# hexapod_mk2_leg_v0_0.net
KiCad netlist of a schematic drawn in EAGLE
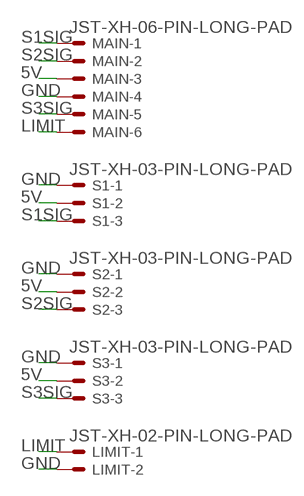
[diagram p0: schematic, sheet 1]

(export (version "E")
  (design (tool "Eeschema 10.0.6"))
  (components
    (comp (ref "LIMIT")
      (value "JST-XH-02-PIN-LONG-PAD")
      (footprint "eagle-import:JST-XH-02-PACKAGE-LONG-PAD")
      (libsource (lib "eagle-import") (part "JST-XH-02-PIN-LONG-PAD"))
    )
    (comp (ref "MAIN")
      (value "JST-XH-06-PIN-LONG-PAD")
      (footprint "eagle-import:JST-XH-06-PACKAGE-LONG-PAD")
      (libsource (lib "eagle-import") (part "JST-XH-06-PIN-LONG-PAD"))
    )
    (comp (ref "S1")
      (value "JST-XH-03-PIN-LONG-PAD")
      (footprint "eagle-import:JST-XH-03-PACKAGE-LONG-PAD")
      (libsource (lib "eagle-import") (part "JST-XH-03-PIN-LONG-PAD"))
    )
    (comp (ref "S2")
      (value "JST-XH-03-PIN-LONG-PAD")
      (footprint "eagle-import:JST-XH-03-PACKAGE-LONG-PAD")
      (libsource (lib "eagle-import") (part "JST-XH-03-PIN-LONG-PAD"))
    )
    (comp (ref "S3")
      (value "JST-XH-03-PIN-LONG-PAD")
      (footprint "eagle-import:JST-XH-03-PACKAGE-LONG-PAD")
      (libsource (lib "eagle-import") (part "JST-XH-03-PIN-LONG-PAD"))
    )
  )
  (nets
    (net (code "1") (name "/5V") (class "Default")
      (node (ref "MAIN") (pin "3") (pinfunction "S_3") (pintype "passive"))
      (node (ref "S1") (pin "2") (pinfunction "S_2") (pintype "passive"))
      (node (ref "S2") (pin "2") (pinfunction "S_2") (pintype "passive"))
      (node (ref "S3") (pin "2") (pinfunction "S_2") (pintype "passive"))
    )
    (net (code "2") (name "/GND") (class "Default")
      (node (ref "LIMIT") (pin "2") (pinfunction "S_2") (pintype "passive"))
      (node (ref "MAIN") (pin "4") (pinfunction "S_4") (pintype "passive"))
      (node (ref "S1") (pin "1") (pinfunction "S_1") (pintype "passive"))
      (node (ref "S2") (pin "1") (pinfunction "S_1") (pintype "passive"))
      (node (ref "S3") (pin "1") (pinfunction "S_1") (pintype "passive"))
    )
    (net (code "3") (name "/LIMIT") (class "Default")
      (node (ref "LIMIT") (pin "1") (pinfunction "S_1") (pintype "passive"))
      (node (ref "MAIN") (pin "6") (pinfunction "S_6") (pintype "passive"))
    )
    (net (code "4") (name "/S1SIG") (class "Default")
      (node (ref "MAIN") (pin "1") (pinfunction "S_1") (pintype "passive"))
      (node (ref "S1") (pin "3") (pinfunction "S_3") (pintype "passive"))
    )
    (net (code "5") (name "/S2SIG") (class "Default")
      (node (ref "MAIN") (pin "2") (pinfunction "S_2") (pintype "passive"))
      (node (ref "S2") (pin "3") (pinfunction "S_3") (pintype "passive"))
    )
    (net (code "6") (name "/S3SIG") (class "Default")
      (node (ref "MAIN") (pin "5") (pinfunction "S_5") (pintype "passive"))
      (node (ref "S3") (pin "3") (pinfunction "S_3") (pintype "passive"))
    )
  )
)
